# driver_T_1.net
KiCad netlist of a schematic drawn in Altium Designer
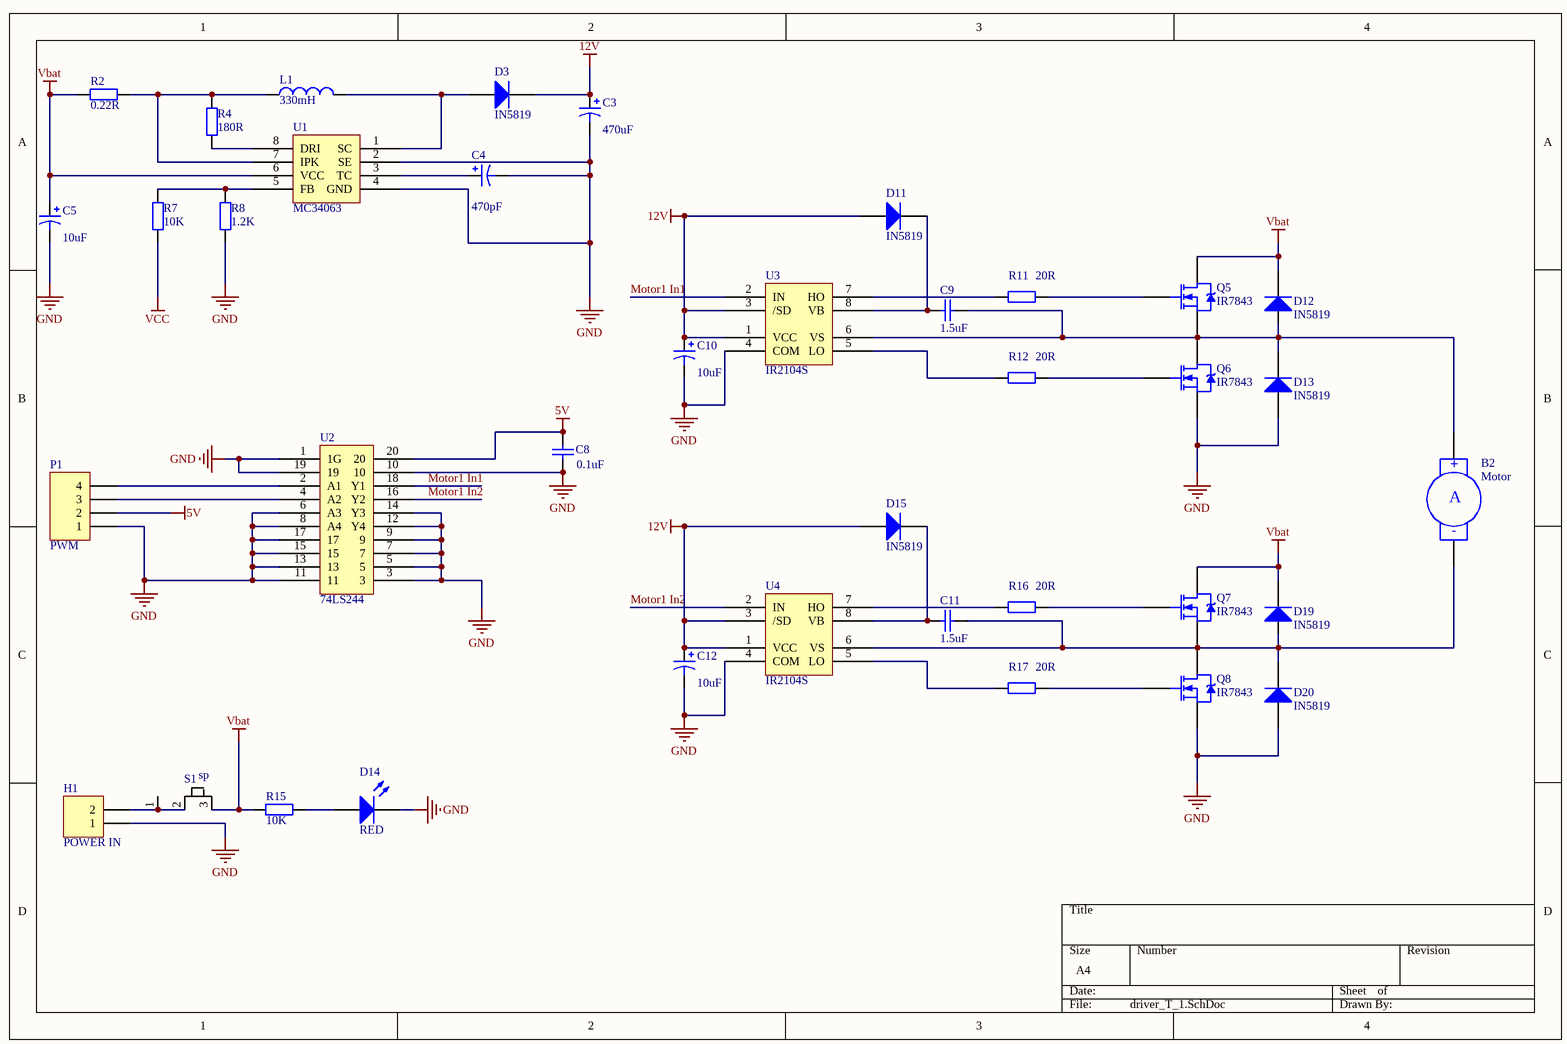
[diagram p0: driver_T_1.SchDoc]

(export (version "E")
  (design (tool "Eeschema 10.0.6"))
  (components
    (comp (ref "B2")
      (value "Motor")
      (footprint "KF301-2P")
      (description "Servo Motor")
      (fields (field (name "PUBLISHER") "Altium Limited"))
      (libsource (lib "Miscellaneous Devices") (part "Motor Servo"))
    )
    (comp (ref "C3")
      (value "470uF")
      (footprint "RB5-10.5")
      (description "Polarized Capacitor (Radial)")
      (fields (field (name "Comment") "Cap Pol1") (field (name "PUBLISHER") "Altium Limited"))
      (libsource (lib "Miscellaneous Devices") (part "Cap Pol1"))
    )
    (comp (ref "C4")
      (value "470pF")
      (footprint "0805(2012)")
      (description "Polarized Capacitor (Radial)")
      (fields (field (name "Comment") "Cap Pol1") (field (name "PUBLISHER") "Altium Limited"))
      (libsource (lib "Miscellaneous Devices") (part "Cap Pol1"))
    )
    (comp (ref "C5")
      (value "10uF")
      (footprint "0805(2012)")
      (description "Polarized Capacitor (Radial)")
      (fields (field (name "Comment") "Cap Pol1") (field (name "PUBLISHER") "Altium Limited"))
      (libsource (lib "Miscellaneous Devices") (part "Cap Pol1"))
    )
    (comp (ref "C8")
      (value "0.1uF")
      (footprint "0805(2012)")
      (description "Capacitor")
      (fields (field (name "Comment") "Cap") (field (name "PUBLISHER") "Altium Limited"))
      (libsource (lib "Miscellaneous Devices") (part "Cap"))
    )
    (comp (ref "C9")
      (value "1.5uF")
      (footprint "0805(2012)")
      (description "Capacitor")
      (fields (field (name "Comment") "Cap") (field (name "PUBLISHER") "Altium Limited"))
      (libsource (lib "Miscellaneous Devices") (part "Cap"))
    )
    (comp (ref "C10")
      (value "10uF")
      (footprint "0805(2012)")
      (description "Polarized Capacitor (Radial)")
      (fields (field (name "Comment") "Cap Pol1") (field (name "PUBLISHER") "Altium Limited"))
      (libsource (lib "Miscellaneous Devices") (part "Cap Pol1"))
    )
    (comp (ref "C11")
      (value "1.5uF")
      (footprint "0805(2012)")
      (description "Capacitor")
      (fields (field (name "Comment") "Cap") (field (name "PUBLISHER") "Altium Limited"))
      (libsource (lib "Miscellaneous Devices") (part "Cap"))
    )
    (comp (ref "C12")
      (value "10uF")
      (footprint "0805(2012)")
      (description "Polarized Capacitor (Radial)")
      (fields (field (name "Comment") "Cap Pol1") (field (name "PUBLISHER") "Altium Limited"))
      (libsource (lib "Miscellaneous Devices") (part "Cap Pol1"))
    )
    (comp (ref "D3")
      (value "IN5819")
      (footprint "0805(2012)")
      (description "Default Diode")
      (fields (field (name "PUBLISHER") "Altium Limited"))
      (libsource (lib "Miscellaneous Devices") (part "Diode"))
    )
    (comp (ref "D11")
      (value "IN5819")
      (footprint "0805(2012)")
      (description "Default Diode")
      (fields (field (name "PUBLISHER") "Altium Limited"))
      (libsource (lib "Miscellaneous Devices") (part "Diode"))
    )
    (comp (ref "D12")
      (value "IN5819")
      (footprint "0805(2012)")
      (description "Default Diode")
      (fields (field (name "PUBLISHER") "Altium Limited"))
      (libsource (lib "Miscellaneous Devices") (part "Diode"))
    )
    (comp (ref "D13")
      (value "IN5819")
      (footprint "0805(2012)")
      (description "Default Diode")
      (fields (field (name "PUBLISHER") "Altium Limited"))
      (libsource (lib "Miscellaneous Devices") (part "Diode"))
    )
    (comp (ref "D14")
      (value "RED")
      (footprint "0805")
      (description "Typical RED, GREEN, YELLOW, AMBER GaAs LED")
      (fields (field (name "PUBLISHER") "Altium Limited"))
      (libsource (lib "LY") (part "LED2"))
    )
    (comp (ref "D15")
      (value "IN5819")
      (footprint "0805(2012)")
      (description "Default Diode")
      (fields (field (name "PUBLISHER") "Altium Limited"))
      (libsource (lib "Miscellaneous Devices") (part "Diode"))
    )
    (comp (ref "D19")
      (value "IN5819")
      (footprint "0805(2012)")
      (description "Default Diode")
      (fields (field (name "PUBLISHER") "Altium Limited"))
      (libsource (lib "Miscellaneous Devices") (part "Diode"))
    )
    (comp (ref "D20")
      (value "IN5819")
      (footprint "0805(2012)")
      (description "Default Diode")
      (fields (field (name "PUBLISHER") "Altium Limited"))
      (libsource (lib "Miscellaneous Devices") (part "Diode"))
    )
    (comp (ref "H1")
      (value "POWER IN")
      (footprint "KF301-2P")
      (description "Header, 2-Pin, Right Angle")
      (fields (field (name "PUBLISHER") "Altium Limited"))
      (libsource (lib "Miscellaneous Connectors") (part "Header 2H"))
    )
    (comp (ref "L1")
      (value "330mH")
      (footprint "电感8*8")
      (description "Inductor")
      (fields (field (name "PUBLISHER") "Altium Limited"))
      (libsource (lib "LY") (part "Inductor"))
    )
    (comp (ref "P1")
      (value "PWM")
      (footprint "PIN-4")
      (description "Header, 4-Pin")
      (fields (field (name "PUBLISHER") "Altium Limited"))
      (libsource (lib "Miscellaneous Connectors") (part "Header 4"))
    )
    (comp (ref "Q5")
      (value "IR7843")
      (footprint "LR7843")
      (description "N-Channel Power MOSFET")
      (fields (field (name "PUBLISHER") "Altium Limited"))
      (libsource (lib "PowerIn") (part "IR7843"))
    )
    (comp (ref "Q6")
      (value "IR7843")
      (footprint "LR7843")
      (description "N-Channel Power MOSFET")
      (fields (field (name "PUBLISHER") "Altium Limited"))
      (libsource (lib "PowerIn") (part "IR7843"))
    )
    (comp (ref "Q7")
      (value "IR7843")
      (footprint "LR7843")
      (description "N-Channel Power MOSFET")
      (fields (field (name "PUBLISHER") "Altium Limited"))
      (libsource (lib "PowerIn") (part "IR7843"))
    )
    (comp (ref "Q8")
      (value "IR7843")
      (footprint "LR7843")
      (description "N-Channel Power MOSFET")
      (fields (field (name "PUBLISHER") "Altium Limited"))
      (libsource (lib "PowerIn") (part "IR7843"))
    )
    (comp (ref "R2")
      (value "0.22R")
      (footprint "0805(2012)")
      (description "Resistor")
      (fields (field (name "Comment") "Res2") (field (name "PUBLISHER") "Altium Limited"))
      (libsource (lib "LY") (part "Res2"))
    )
    (comp (ref "R4")
      (value "180R")
      (footprint "0805(2012)")
      (description "Resistor")
      (fields (field (name "Comment") "Res2") (field (name "PUBLISHER") "Altium Limited"))
      (libsource (lib "") (part "Res2_1"))
    )
    (comp (ref "R7")
      (value "10K")
      (footprint "0805(2012)")
      (description "Resistor")
      (fields (field (name "Comment") "Res2") (field (name "PUBLISHER") "Altium Limited"))
      (libsource (lib "") (part "Res2_1"))
    )
    (comp (ref "R8")
      (value "1.2K")
      (footprint "0805(2012)")
      (description "Resistor")
      (fields (field (name "Comment") "Res2") (field (name "PUBLISHER") "Altium Limited"))
      (libsource (lib "") (part "Res2_1"))
    )
    (comp (ref "R11")
      (value "20R")
      (footprint "0805(2012)")
      (description "Resistor")
      (fields (field (name "Comment") "Res2") (field (name "PUBLISHER") "Altium Limited"))
      (libsource (lib "LY") (part "Res2"))
    )
    (comp (ref "R12")
      (value "20R")
      (footprint "0805(2012)")
      (description "Resistor")
      (fields (field (name "Comment") "Res2") (field (name "PUBLISHER") "Altium Limited"))
      (libsource (lib "LY") (part "Res2"))
    )
    (comp (ref "R15")
      (value "10K")
      (footprint "0603")
      (description "Resistor")
      (fields (field (name "Comment") "Res2") (field (name "PUBLISHER") "Altium Limited"))
      (libsource (lib "LY") (part "Res2"))
    )
    (comp (ref "R16")
      (value "20R")
      (footprint "0805(2012)")
      (description "Resistor")
      (fields (field (name "Comment") "Res2") (field (name "PUBLISHER") "Altium Limited"))
      (libsource (lib "LY") (part "Res2"))
    )
    (comp (ref "R17")
      (value "20R")
      (footprint "0805(2012)")
      (description "Resistor")
      (fields (field (name "Comment") "Res2") (field (name "PUBLISHER") "Altium Limited"))
      (libsource (lib "LY") (part "Res2"))
    )
    (comp (ref "S1") (value "sp") (footprint "SWICH-3") (libsource (lib "MOS motor") (part "sp")))
    (comp (ref "U1") (value "MC34063") (footprint "MC34063") (libsource (lib "LY") (part "MC34063")))
    (comp (ref "U2") (value "74LS244") (footprint "74LS244") (libsource (lib "LY") (part "74LS244")))
    (comp (ref "U3") (value "IR2104S") (footprint "IR2104S") (libsource (lib "LY") (part "IR2104S")))
    (comp (ref "U4") (value "IR2104S") (footprint "IR2104S") (libsource (lib "LY") (part "IR2104S")))
  )
  (nets
    (net (code "1") (name "/Motor1 In1") (class "Default")
      (node (ref "U2") (pin "18") (pinfunction "Y1_18") (pintype "passive"))
      (node (ref "U3") (pin "2") (pinfunction "IN_2") (pintype "passive"))
    )
    (net (code "2") (name "/Motor1 In2") (class "Default")
      (node (ref "U2") (pin "16") (pinfunction "Y2_16") (pintype "passive"))
      (node (ref "U4") (pin "2") (pinfunction "IN_2") (pintype "passive"))
    )
    (net (code "3") (name "5V") (class "Default")
      (node (ref "C8") (pin "2") (pinfunction "2_2") (pintype "passive"))
      (node (ref "P1") (pin "2") (pinfunction "2_2") (pintype "passive"))
      (node (ref "U2") (pin "20") (pinfunction "20_20") (pintype "passive"))
    )
    (net (code "4") (name "12V") (class "Default")
      (node (ref "C10") (pin "1") (pinfunction "1_1") (pintype "passive"))
      (node (ref "C12") (pin "1") (pinfunction "1_1") (pintype "passive"))
      (node (ref "C3") (pin "1") (pinfunction "1_1") (pintype "passive"))
      (node (ref "D11") (pin "1") (pinfunction "A_1") (pintype "passive"))
      (node (ref "D15") (pin "1") (pinfunction "A_1") (pintype "passive"))
      (node (ref "D3") (pin "2") (pinfunction "K_2") (pintype "passive"))
      (node (ref "U3") (pin "1") (pinfunction "VCC_1") (pintype "passive"))
      (node (ref "U3") (pin "3") (pinfunction "/SD_3") (pintype "passive"))
      (node (ref "U4") (pin "1") (pinfunction "VCC_1") (pintype "passive"))
      (node (ref "U4") (pin "3") (pinfunction "/SD_3") (pintype "passive"))
    )
    (net (code "5") (name "GND") (class "Default")
      (node (ref "C10") (pin "2") (pinfunction "2_2") (pintype "passive"))
      (node (ref "C12") (pin "2") (pinfunction "2_2") (pintype "passive"))
      (node (ref "C3") (pin "2") (pinfunction "2_2") (pintype "passive"))
      (node (ref "C4") (pin "2") (pinfunction "2_2") (pintype "passive"))
      (node (ref "C5") (pin "2") (pinfunction "2_2") (pintype "passive"))
      (node (ref "C8") (pin "1") (pinfunction "1_1") (pintype "passive"))
      (node (ref "D13") (pin "1") (pinfunction "A_1") (pintype "passive"))
      (node (ref "D14") (pin "2") (pinfunction "K_2") (pintype "passive"))
      (node (ref "D20") (pin "1") (pinfunction "A_1") (pintype "passive"))
      (node (ref "H1") (pin "1") (pinfunction "1_1") (pintype "passive"))
      (node (ref "P1") (pin "1") (pinfunction "1_1") (pintype "passive"))
      (node (ref "Q6") (pin "3") (pinfunction "S_3") (pintype "passive"))
      (node (ref "Q8") (pin "3") (pinfunction "S_3") (pintype "passive"))
      (node (ref "R8") (pin "1") (pinfunction "1_1") (pintype "passive"))
      (node (ref "U1") (pin "2") (pinfunction "SE_2") (pintype "passive"))
      (node (ref "U1") (pin "4") (pinfunction "GND_4") (pintype "passive"))
      (node (ref "U2") (pin "1") (pinfunction "1G_1") (pintype "passive"))
      (node (ref "U2") (pin "10") (pinfunction "10_10") (pintype "passive"))
      (node (ref "U2") (pin "11") (pinfunction "11_11") (pintype "passive"))
      (node (ref "U2") (pin "12") (pinfunction "Y4_12") (pintype "passive"))
      (node (ref "U2") (pin "13") (pinfunction "13_13") (pintype "passive"))
      (node (ref "U2") (pin "14") (pinfunction "Y3_14") (pintype "passive"))
      (node (ref "U2") (pin "15") (pinfunction "15_15") (pintype "passive"))
      (node (ref "U2") (pin "17") (pinfunction "17_17") (pintype "passive"))
      (node (ref "U2") (pin "19") (pinfunction "19_19") (pintype "passive"))
      (node (ref "U2") (pin "3") (pinfunction "3_3") (pintype "passive"))
      (node (ref "U2") (pin "5") (pinfunction "5_5") (pintype "passive"))
      (node (ref "U2") (pin "6") (pinfunction "A3_6") (pintype "passive"))
      (node (ref "U2") (pin "7") (pinfunction "7_7") (pintype "passive"))
      (node (ref "U2") (pin "8") (pinfunction "A4_8") (pintype "passive"))
      (node (ref "U2") (pin "9") (pinfunction "9_9") (pintype "passive"))
      (node (ref "U3") (pin "4") (pinfunction "COM_4") (pintype "passive"))
      (node (ref "U4") (pin "4") (pinfunction "COM_4") (pintype "passive"))
    )
    (net (code "6") (name "Net-(B2-+)") (class "Default")
      (node (ref "B2") (pin "1") (pinfunction "+_1") (pintype "passive"))
      (node (ref "C9") (pin "1") (pinfunction "1_1") (pintype "passive"))
      (node (ref "D12") (pin "1") (pinfunction "A_1") (pintype "passive"))
      (node (ref "D13") (pin "2") (pinfunction "K_2") (pintype "passive"))
      (node (ref "Q5") (pin "3") (pinfunction "S_3") (pintype "passive"))
      (node (ref "Q6") (pin "2") (pinfunction "D_2") (pintype "passive"))
      (node (ref "U3") (pin "6") (pinfunction "VS_6") (pintype "passive"))
    )
    (net (code "7") (name "Net-(B2--)") (class "Default")
      (node (ref "B2") (pin "2") (pinfunction "-_2") (pintype "passive"))
      (node (ref "C11") (pin "1") (pinfunction "1_1") (pintype "passive"))
      (node (ref "D19") (pin "1") (pinfunction "A_1") (pintype "passive"))
      (node (ref "D20") (pin "2") (pinfunction "K_2") (pintype "passive"))
      (node (ref "Q7") (pin "3") (pinfunction "S_3") (pintype "passive"))
      (node (ref "Q8") (pin "2") (pinfunction "D_2") (pintype "passive"))
      (node (ref "U4") (pin "6") (pinfunction "VS_6") (pintype "passive"))
    )
    (net (code "8") (name "Net-(D3-A)") (class "Default")
      (node (ref "D3") (pin "1") (pinfunction "A_1") (pintype "passive"))
      (node (ref "L1") (pin "2") (pinfunction "2_2") (pintype "passive"))
      (node (ref "U1") (pin "1") (pinfunction "SC_1") (pintype "passive"))
    )
    (net (code "9") (name "Net-(D11-K)") (class "Default")
      (node (ref "C9") (pin "2") (pinfunction "2_2") (pintype "passive"))
      (node (ref "D11") (pin "2") (pinfunction "K_2") (pintype "passive"))
      (node (ref "U3") (pin "8") (pinfunction "VB_8") (pintype "passive"))
    )
    (net (code "10") (name "Net-(D14-A)") (class "Default")
      (node (ref "D14") (pin "1") (pinfunction "A_1") (pintype "passive"))
      (node (ref "R15") (pin "2") (pinfunction "2_2") (pintype "passive"))
    )
    (net (code "11") (name "Net-(D15-K)") (class "Default")
      (node (ref "C11") (pin "2") (pinfunction "2_2") (pintype "passive"))
      (node (ref "D15") (pin "2") (pinfunction "K_2") (pintype "passive"))
      (node (ref "U4") (pin "8") (pinfunction "VB_8") (pintype "passive"))
    )
    (net (code "12") (name "Net-(H1-Pad2)") (class "Default")
      (node (ref "H1") (pin "2") (pinfunction "2_2") (pintype "passive"))
      (node (ref "S1") (pin "1") (pintype "passive"))
      (node (ref "S1") (pin "2") (pintype "passive"))
    )
    (net (code "13") (name "Net-(Q5-G)") (class "Default")
      (node (ref "Q5") (pin "1") (pinfunction "G_1") (pintype "passive"))
      (node (ref "R11") (pin "2") (pinfunction "2_2") (pintype "passive"))
    )
    (net (code "14") (name "Net-(Q6-G)") (class "Default")
      (node (ref "Q6") (pin "1") (pinfunction "G_1") (pintype "passive"))
      (node (ref "R12") (pin "2") (pinfunction "2_2") (pintype "passive"))
    )
    (net (code "15") (name "Net-(Q7-G)") (class "Default")
      (node (ref "Q7") (pin "1") (pinfunction "G_1") (pintype "passive"))
      (node (ref "R16") (pin "2") (pinfunction "2_2") (pintype "passive"))
    )
    (net (code "16") (name "Net-(Q8-G)") (class "Default")
      (node (ref "Q8") (pin "1") (pinfunction "G_1") (pintype "passive"))
      (node (ref "R17") (pin "2") (pinfunction "2_2") (pintype "passive"))
    )
    (net (code "17") (name "Net-(U1-DRI)") (class "Default")
      (node (ref "R4") (pin "1") (pinfunction "1_1") (pintype "passive"))
      (node (ref "U1") (pin "8") (pinfunction "DRI_8") (pintype "passive"))
    )
    (net (code "18") (name "Net-(U1-FB)") (class "Default")
      (node (ref "R7") (pin "2") (pinfunction "2_2") (pintype "passive"))
      (node (ref "R8") (pin "2") (pinfunction "2_2") (pintype "passive"))
      (node (ref "U1") (pin "5") (pinfunction "FB_5") (pintype "passive"))
    )
    (net (code "19") (name "Net-(U1-IPK)") (class "Default")
      (node (ref "L1") (pin "1") (pinfunction "1_1") (pintype "passive"))
      (node (ref "R2") (pin "2") (pinfunction "2_2") (pintype "passive"))
      (node (ref "R4") (pin "2") (pinfunction "2_2") (pintype "passive"))
      (node (ref "U1") (pin "7") (pinfunction "IPK_7") (pintype "passive"))
    )
    (net (code "20") (name "Net-(U1-TC)") (class "Default")
      (node (ref "C4") (pin "1") (pinfunction "1_1") (pintype "passive"))
      (node (ref "U1") (pin "3") (pinfunction "TC_3") (pintype "passive"))
    )
    (net (code "21") (name "Net-(U2-A1)") (class "Default")
      (node (ref "P1") (pin "4") (pinfunction "4_4") (pintype "passive"))
      (node (ref "U2") (pin "2") (pinfunction "A1_2") (pintype "passive"))
    )
    (net (code "22") (name "Net-(U2-A2)") (class "Default")
      (node (ref "P1") (pin "3") (pinfunction "3_3") (pintype "passive"))
      (node (ref "U2") (pin "4") (pinfunction "A2_4") (pintype "passive"))
    )
    (net (code "23") (name "Net-(U3-HO)") (class "Default")
      (node (ref "R11") (pin "1") (pinfunction "1_1") (pintype "passive"))
      (node (ref "U3") (pin "7") (pinfunction "HO_7") (pintype "passive"))
    )
    (net (code "24") (name "Net-(U3-LO)") (class "Default")
      (node (ref "R12") (pin "1") (pinfunction "1_1") (pintype "passive"))
      (node (ref "U3") (pin "5") (pinfunction "LO_5") (pintype "passive"))
    )
    (net (code "25") (name "Net-(U4-HO)") (class "Default")
      (node (ref "R16") (pin "1") (pinfunction "1_1") (pintype "passive"))
      (node (ref "U4") (pin "7") (pinfunction "HO_7") (pintype "passive"))
    )
    (net (code "26") (name "Net-(U4-LO)") (class "Default")
      (node (ref "R17") (pin "1") (pinfunction "1_1") (pintype "passive"))
      (node (ref "U4") (pin "5") (pinfunction "LO_5") (pintype "passive"))
    )
    (net (code "27") (name "VCC") (class "Default")
      (node (ref "R7") (pin "1") (pinfunction "1_1") (pintype "passive"))
    )
    (net (code "28") (name "Vbat") (class "Default")
      (node (ref "C5") (pin "1") (pinfunction "1_1") (pintype "passive"))
      (node (ref "D12") (pin "2") (pinfunction "K_2") (pintype "passive"))
      (node (ref "D19") (pin "2") (pinfunction "K_2") (pintype "passive"))
      (node (ref "Q5") (pin "2") (pinfunction "D_2") (pintype "passive"))
      (node (ref "Q7") (pin "2") (pinfunction "D_2") (pintype "passive"))
      (node (ref "R15") (pin "1") (pinfunction "1_1") (pintype "passive"))
      (node (ref "R2") (pin "1") (pinfunction "1_1") (pintype "passive"))
      (node (ref "S1") (pin "3") (pintype "passive"))
      (node (ref "U1") (pin "6") (pinfunction "VCC_6") (pintype "passive"))
    )
  )
)
